# TPIC8101DW.net
KiCad netlist of a schematic drawn in Altium Designer
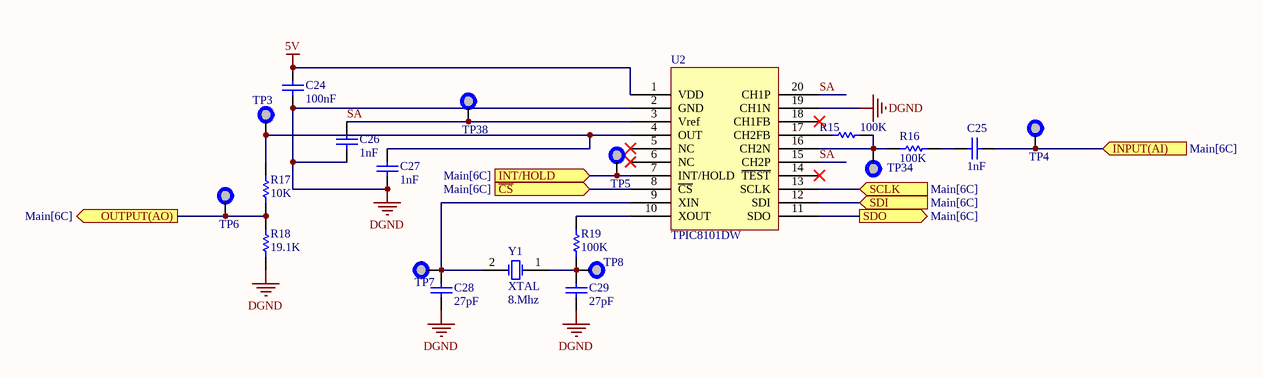
[diagram p0: TPIC8101DW.SchDoc]

(export (version "E")
  (design (tool "Eeschema 10.0.6"))
  (components
    (comp (ref "C24")
      (value "100nF")
      (footprint "0603c")
      (description "LOW ESR")
      (fields (field (name "PUBLISHER") "Altium Limited"))
      (libsource (lib "Miscellaneous Devices") (part "Cap"))
    )
    (comp (ref "C25")
      (value "1nF")
      (footprint "0805C")
      (description "LOW ESR")
      (fields (field (name "PUBLISHER") "Altium Limited"))
      (libsource (lib "Miscellaneous Devices") (part "Cap"))
    )
    (comp (ref "C26")
      (value "1nF")
      (footprint "0805C")
      (description "LOW ESR")
      (fields (field (name "PUBLISHER") "Altium Limited"))
      (libsource (lib "Miscellaneous Devices") (part "Cap"))
    )
    (comp (ref "C27")
      (value "1nF")
      (footprint "0805C")
      (description "LOW ESR")
      (fields (field (name "PUBLISHER") "Altium Limited"))
      (libsource (lib "Miscellaneous Devices") (part "Cap"))
    )
    (comp (ref "C28")
      (value "27pF")
      (footprint "0805C")
      (description "LOW ESR")
      (fields (field (name "Comment") "1nF") (field (name "PUBLISHER") "Altium Limited"))
      (libsource (lib "Miscellaneous Devices") (part "Cap"))
    )
    (comp (ref "C29")
      (value "27pF")
      (footprint "0805C")
      (description "LOW ESR")
      (fields (field (name "PUBLISHER") "Altium Limited"))
      (libsource (lib "Miscellaneous Devices") (part "Cap"))
    )
    (comp (ref "R15")
      (value "100K")
      (footprint "0805")
      (description "Resistor")
      (fields (field (name "PUBLISHER") "Altium Limited"))
      (libsource (lib "Miscellaneous Devices") (part "Res1"))
    )
    (comp (ref "R16")
      (value "100K")
      (footprint "0805")
      (description "Resistor")
      (fields (field (name "PUBLISHER") "Altium Limited"))
      (libsource (lib "Miscellaneous Devices") (part "Res1"))
    )
    (comp (ref "R17")
      (value "10K")
      (footprint "0805")
      (description "Resistor")
      (fields (field (name "PUBLISHER") "Altium Limited"))
      (libsource (lib "Miscellaneous Devices") (part "Res1"))
    )
    (comp (ref "R18")
      (value "19.1K")
      (footprint "0805")
      (description "Resistor")
      (fields (field (name "PUBLISHER") "Altium Limited"))
      (libsource (lib "Miscellaneous Devices") (part "Res1"))
    )
    (comp (ref "R19")
      (value "100K")
      (footprint "0805")
      (description "Resistor")
      (fields (field (name "PUBLISHER") "Altium Limited"))
      (libsource (lib "Miscellaneous Devices") (part "Res1"))
    )
    (comp (ref "TP3") (value "TestPoint") (footprint "TP") (libsource (lib "SchlibV0.1") (part "TestPoint")))
    (comp (ref "TP4") (value "TestPoint") (footprint "TP") (libsource (lib "SchlibV0.1") (part "TestPoint")))
    (comp (ref "TP5") (value "TestPoint") (footprint "TP") (libsource (lib "SchlibV0.1") (part "TestPoint")))
    (comp (ref "TP6") (value "TestPoint") (footprint "TP") (libsource (lib "SchlibV0.1") (part "TestPoint")))
    (comp (ref "TP7") (value "TestPoint") (footprint "TP") (libsource (lib "SchlibV0.1") (part "TestPoint")))
    (comp (ref "TP8") (value "TestPoint") (footprint "TP") (libsource (lib "SchlibV0.1") (part "TestPoint")))
    (comp (ref "TP34") (value "TestPoint") (footprint "TP") (libsource (lib "SchlibV0.1") (part "TestPoint")))
    (comp (ref "TP38") (value "TestPoint") (footprint "TP") (libsource (lib "SchlibV0.1") (part "TestPoint")))
    (comp (ref "U2")
      (value "TPIC8101DW")
      (footprint "SOIC-20")
      (description "Knock, SO20")
      (fields (field (name "MANUFACTURER") "TI"))
      (libsource (lib "Lib") (part "TPIC8101DW"))
    )
    (comp (ref "Y1")
      (value "XTAL")
      (footprint "XTAL")
      (description "Crystal Oscillator")
      (fields (field (name "ALTIUM_VALUE") "8.Mhz") (field (name "PUBLISHER") "Altium Limited"))
      (libsource (lib "Miscellaneous Devices") (part "XTAL"))
    )
  )
  (nets
    (net (code "1") (name "/INPUT(AI)") (class "Default")
      (node (ref "C25") (pin "1") (pinfunction "1_1") (pintype "passive"))
      (node (ref "TP4") (pin "1") (pintype "passive"))
    )
    (net (code "2") (name "/INT{slash}HOLD") (class "Default")
      (node (ref "TP5") (pin "1") (pintype "passive"))
      (node (ref "U2") (pin "7") (pinfunction "INT/HOLD_7") (pintype "passive"))
    )
    (net (code "3") (name "/OUTPUT(AO)") (class "Default")
      (node (ref "R17") (pin "1") (pinfunction "1_1") (pintype "passive"))
      (node (ref "R18") (pin "2") (pinfunction "2_2") (pintype "passive"))
      (node (ref "TP6") (pin "1") (pintype "passive"))
    )
    (net (code "4") (name "/SA") (class "Default")
      (node (ref "C26") (pin "2") (pinfunction "2_2") (pintype "passive"))
      (node (ref "TP38") (pin "1") (pintype "passive"))
      (node (ref "U2") (pin "15") (pinfunction "CH2P_15") (pintype "passive"))
      (node (ref "U2") (pin "20") (pinfunction "CH1P_20") (pintype "passive"))
      (node (ref "U2") (pin "3") (pinfunction "Vref_3") (pintype "passive"))
    )
    (net (code "5") (name "/SCLK") (class "Default")
      (node (ref "U2") (pin "13") (pinfunction "SCLK_13") (pintype "passive"))
    )
    (net (code "6") (name "/SDI") (class "Default")
      (node (ref "U2") (pin "12") (pinfunction "SDI_12") (pintype "passive"))
    )
    (net (code "7") (name "/SDO") (class "Default")
      (node (ref "U2") (pin "11") (pinfunction "SDO_11") (pintype "passive"))
    )
    (net (code "8") (name "/~{CS}") (class "Default")
      (node (ref "U2") (pin "8") (pinfunction "~{CS}_8") (pintype "passive"))
    )
    (net (code "9") (name "5V") (class "Default")
      (node (ref "C24") (pin "1") (pinfunction "1_1") (pintype "passive"))
      (node (ref "U2") (pin "1") (pinfunction "VDD_1") (pintype "passive"))
    )
    (net (code "10") (name "DGND") (class "Default")
      (node (ref "C24") (pin "2") (pinfunction "2_2") (pintype "passive"))
      (node (ref "C26") (pin "1") (pinfunction "1_1") (pintype "passive"))
      (node (ref "C27") (pin "1") (pinfunction "1_1") (pintype "passive"))
      (node (ref "C28") (pin "2") (pinfunction "2_2") (pintype "passive"))
      (node (ref "C29") (pin "2") (pinfunction "2_2") (pintype "passive"))
      (node (ref "R18") (pin "1") (pinfunction "1_1") (pintype "passive"))
      (node (ref "U2") (pin "19") (pinfunction "CH1N_19") (pintype "passive"))
      (node (ref "U2") (pin "2") (pinfunction "GND_2") (pintype "passive"))
    )
    (net (code "11") (name "Net-(C25-Pad2)") (class "Default")
      (node (ref "C25") (pin "2") (pinfunction "2_2") (pintype "passive"))
      (node (ref "R16") (pin "2") (pinfunction "2_2") (pintype "passive"))
    )
    (net (code "12") (name "Net-(U2-CH2FB)") (class "Default")
      (node (ref "R15") (pin "1") (pinfunction "1_1") (pintype "passive"))
      (node (ref "U2") (pin "17") (pinfunction "CH2FB_17") (pintype "passive"))
    )
    (net (code "13") (name "Net-(U2-CH2N)") (class "Default")
      (node (ref "R15") (pin "2") (pinfunction "2_2") (pintype "passive"))
      (node (ref "R16") (pin "1") (pinfunction "1_1") (pintype "passive"))
      (node (ref "TP34") (pin "1") (pintype "passive"))
      (node (ref "U2") (pin "16") (pinfunction "CH2N_16") (pintype "passive"))
    )
    (net (code "14") (name "Net-(U2-OUT)") (class "Default")
      (node (ref "C27") (pin "2") (pinfunction "2_2") (pintype "passive"))
      (node (ref "R17") (pin "2") (pinfunction "2_2") (pintype "passive"))
      (node (ref "TP3") (pin "1") (pintype "passive"))
      (node (ref "U2") (pin "4") (pinfunction "OUT_4") (pintype "passive"))
    )
    (net (code "15") (name "Net-(U2-XIN)") (class "Default")
      (node (ref "C28") (pin "1") (pinfunction "1_1") (pintype "passive"))
      (node (ref "TP7") (pin "1") (pintype "passive"))
      (node (ref "U2") (pin "9") (pinfunction "XIN_9") (pintype "passive"))
      (node (ref "Y1") (pin "2") (pinfunction "OSC2_2") (pintype "passive"))
    )
    (net (code "16") (name "Net-(U2-XOUT)") (class "Default")
      (node (ref "R19") (pin "2") (pinfunction "2_2") (pintype "passive"))
      (node (ref "U2") (pin "10") (pinfunction "XOUT_10") (pintype "passive"))
    )
    (net (code "17") (name "Net-(Y1-OSC1)") (class "Default")
      (node (ref "C29") (pin "1") (pinfunction "1_1") (pintype "passive"))
      (node (ref "R19") (pin "1") (pinfunction "1_1") (pintype "passive"))
      (node (ref "TP8") (pin "1") (pintype "passive"))
      (node (ref "Y1") (pin "1") (pinfunction "OSC1_1") (pintype "passive"))
    )
    (net (code "18") (name "unconnected-(U2-CH1FB-Pad18)") (class "Default")
      (node (ref "U2") (pin "18") (pinfunction "CH1FB_18") (pintype "passive+no_connect"))
    )
    (net (code "19") (name "unconnected-(U2-NC-Pad5)") (class "Default")
      (node (ref "U2") (pin "5") (pinfunction "NC_5") (pintype "passive+no_connect"))
    )
    (net (code "20") (name "unconnected-(U2-NC-Pad6)") (class "Default")
      (node (ref "U2") (pin "6") (pinfunction "NC_6") (pintype "passive+no_connect"))
    )
    (net (code "21") (name "unconnected-(U2-~{TEST}-Pad14)") (class "Default")
      (node (ref "U2") (pin "14") (pinfunction "~{TEST}_14") (pintype "passive+no_connect"))
    )
  )
)
